# P04_Processor_2_or_3_USB_and_Serial.net
KiCad netlist of a schematic drawn in Altium Designer
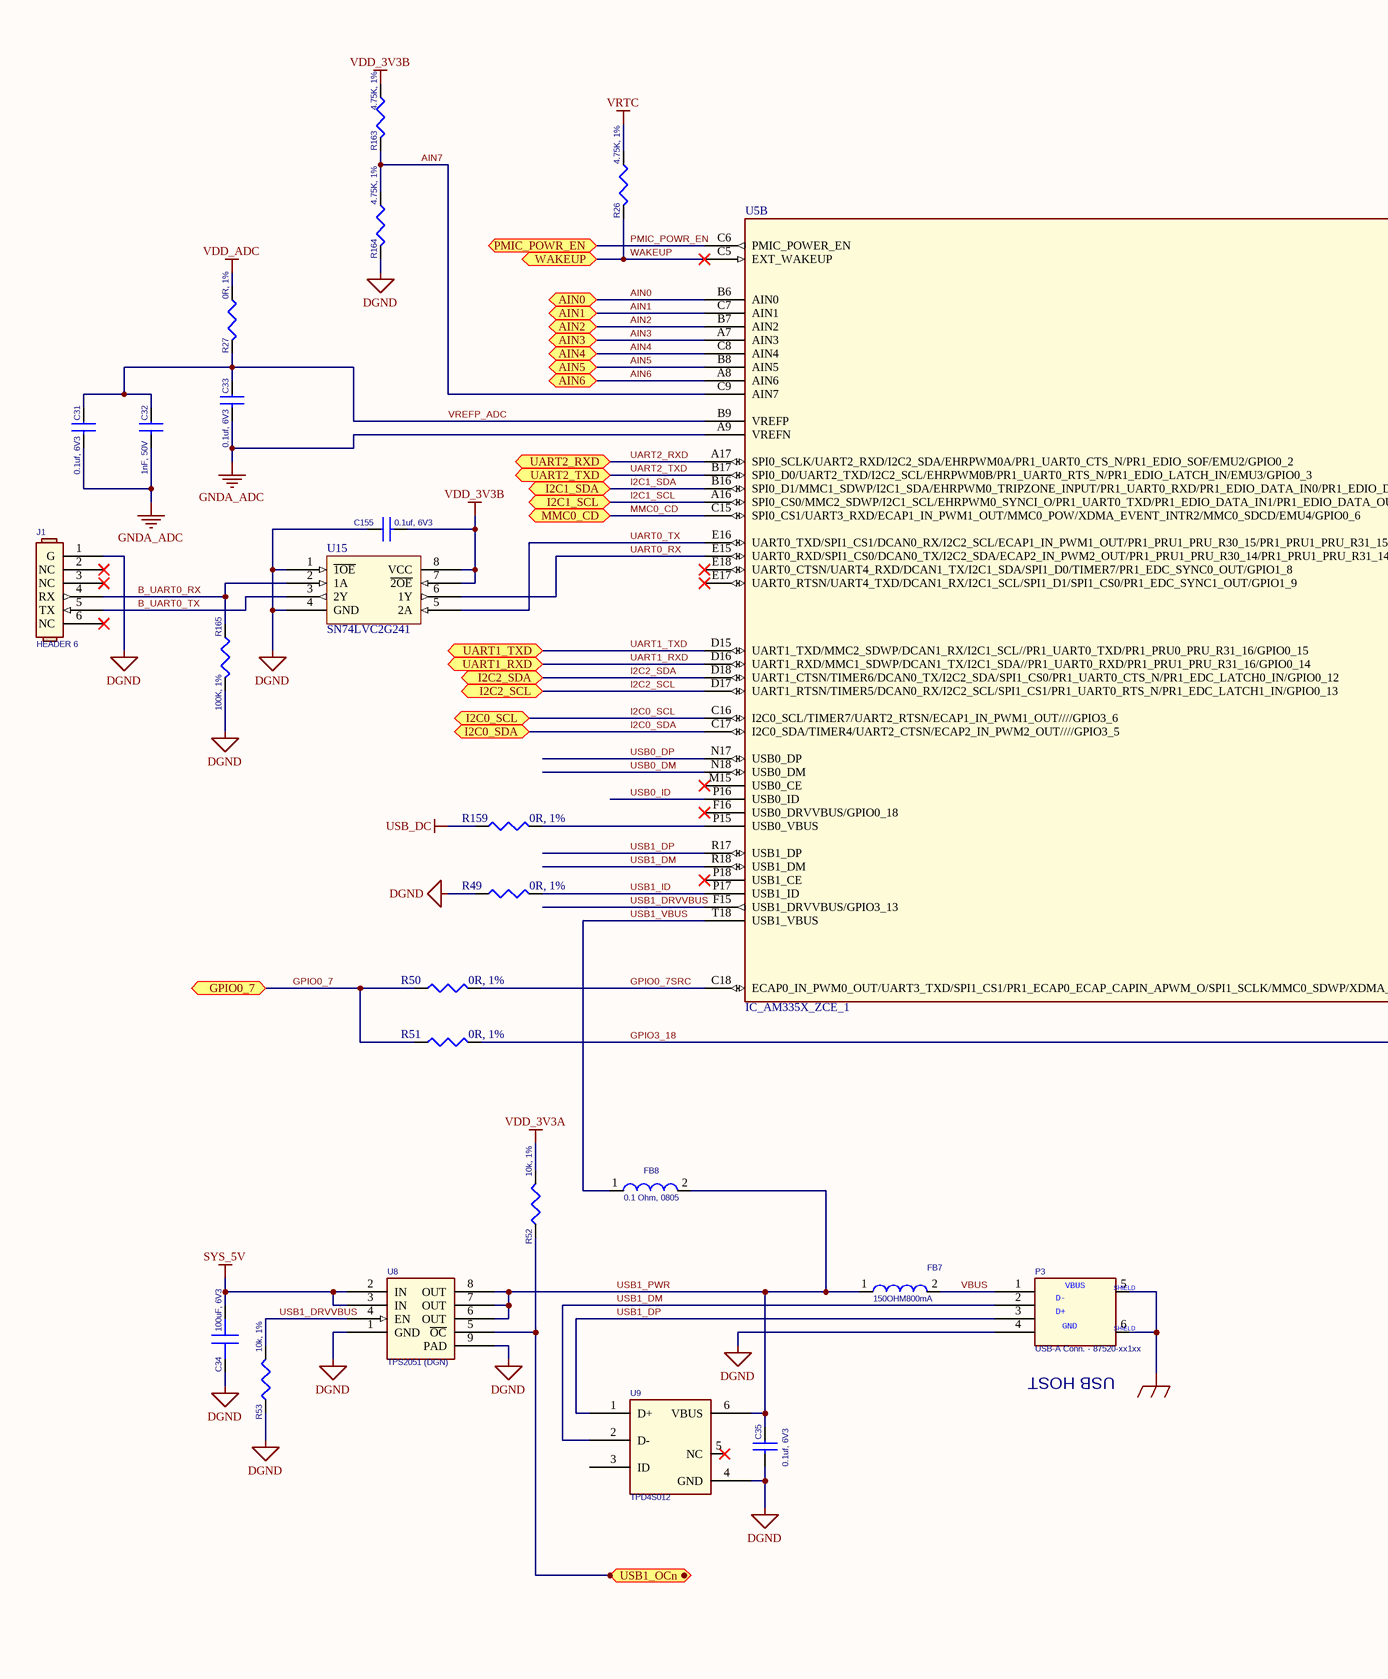
[diagram p0: P04_Processor 2 or 3, USB and Serial.SchDoc, left]
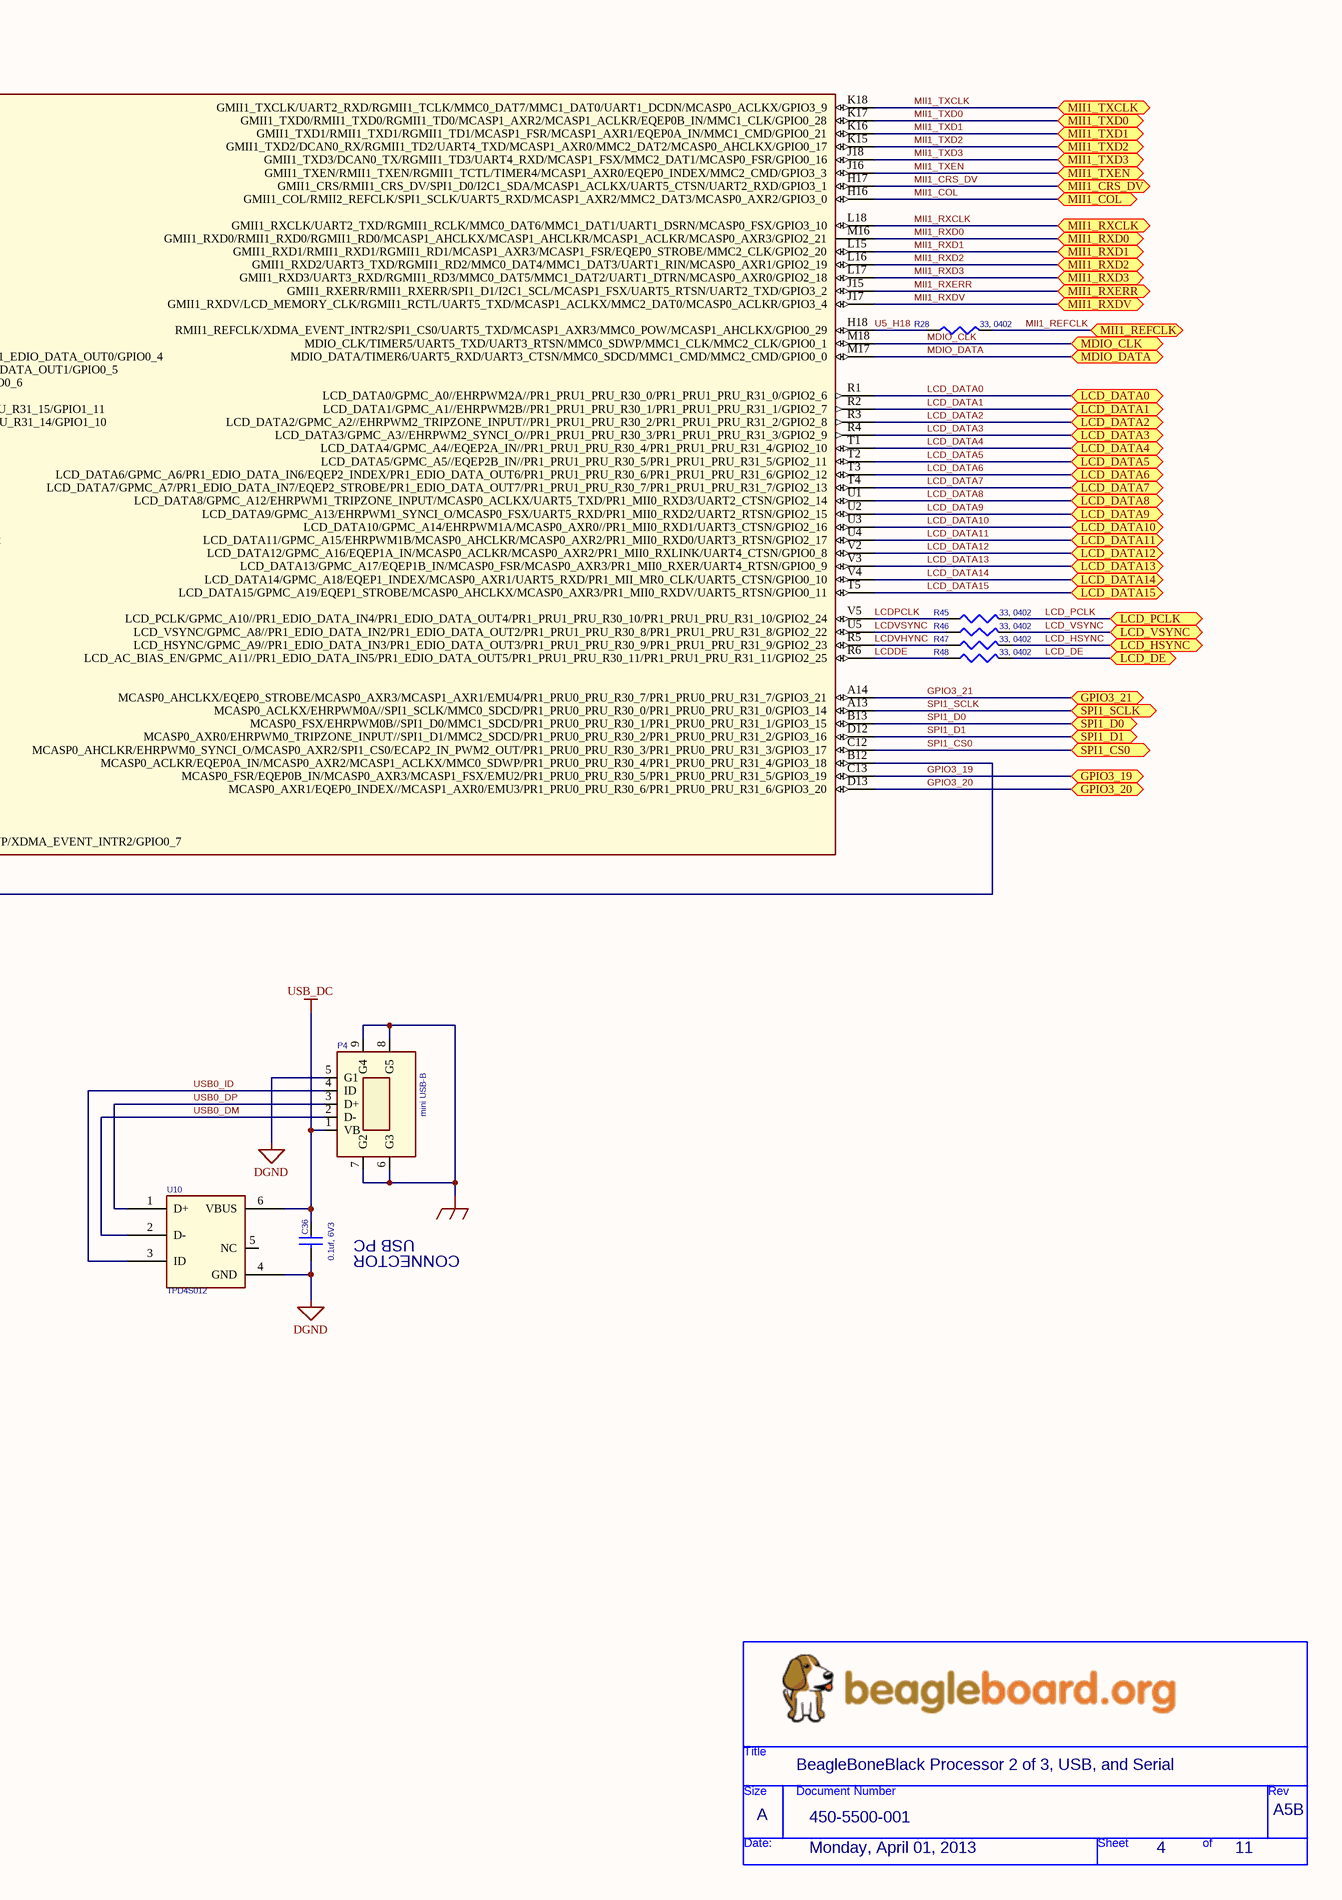
[diagram p1: P04_Processor 2 or 3, USB and Serial.SchDoc, right]

(export (version "E")
  (design (tool "Eeschema 10.0.6"))
  (components
    (comp (ref "C31")
      (value "0.1uf, 6V3")
      (footprint "402")
      (description "CAP CER 0.1UF 6.3V 10% X5R 0402")
      (fields
        (field (name "MANUFACTURER") "TDK Corporation")
        (field (name "MANUFACTURER PART NUMBER") "C1005X5R0J104K050BA")
      )
      (libsource (lib "BEAGLEBONEBLACK_REV A5B") (part "CAP_0.1uF_X7R_16V_10% 0402"))
    )
    (comp (ref "C32")
      (value "1nF, 50V")
      (footprint "402")
      (description "CAP CER 1000PF 16V 10% X7R 0402")
      (fields
        (field (name "MANUFACTURER") "Yageo")
        (field (name "MANUFACTURER PART NUMBER") "CC0402KRX7R7BB102")
      )
      (libsource (lib "BEAGLEBONEBLACK_REV A5B") (part "CAP_0.001_X7R_50V_5%_0402"))
    )
    (comp (ref "C33")
      (value "0.1uf, 6V3")
      (footprint "402")
      (description "CAP CER 0.1UF 6.3V 10% X5R 0402")
      (fields
        (field (name "MANUFACTURER") "TDK Corporation")
        (field (name "MANUFACTURER PART NUMBER") "C1005X5R0J104K050BA")
      )
      (libsource (lib "BEAGLEBONEBLACK_REV A5B") (part "CAP_0.1uF_X7R_16V_10% 0402"))
    )
    (comp (ref "C34")
      (value "100uF, 6V3")
      (footprint "RD205SMD_250D")
      (description "CAP ALUM 100UF 6.3V 20% SMD")
      (fields
        (field (name "MANUFACTURER") "Cornell Dubilier Electronics (CDE)")
        (field (name "MANUFACTURER PART NUMBER") "AVE107M06D16T-F")
      )
      (libsource (lib "BEAGLEBONEBLACK_REV A5B") (part "CAP SMD"))
    )
    (comp (ref "C35")
      (value "0.1uf, 6V3")
      (footprint "402")
      (description "CAP CER 0.1UF 6.3V 10% X5R 0402")
      (fields
        (field (name "MANUFACTURER") "TDK Corporation")
        (field (name "MANUFACTURER PART NUMBER") "C1005X5R0J104K050BA")
      )
      (libsource (lib "BEAGLEBONEBLACK_REV A5B") (part "CAP_0.1uF_X7R_16V_10% 0402"))
    )
    (comp (ref "C36")
      (value "0.1uf, 6V3")
      (footprint "402")
      (description "CAP CER 0.1UF 6.3V 10% X5R 0402")
      (fields
        (field (name "MANUFACTURER") "TDK Corporation")
        (field (name "MANUFACTURER PART NUMBER") "C1005X5R0J104K050BA")
      )
      (libsource (lib "BEAGLEBONEBLACK_REV A5B") (part "CAP_0.1uF_X7R_16V_10% 0402"))
    )
    (comp (ref "C155")
      (value "0.1uf, 6V3")
      (footprint "402")
      (description "CAP CER 0.1UF 6.3V 10% X5R 0402")
      (fields
        (field (name "MANUFACTURER") "TDK Corporation")
        (field (name "MANUFACTURER PART NUMBER") "C1005X5R0J104K050BA")
      )
      (libsource (lib "BEAGLEBONEBLACK_REV A5B") (part "CAP_0.1uF_X7R_16V_10% 0402"))
    )
    (comp (ref "FB7")
      (value "150OHM800mA")
      (footprint "SM-7351-IND-0805")
      (description "FERRITE 800MA 150 OHM 0805 SMD")
      (fields (field (name "MFR") "Steward") (field (name "TIINTPARTNUMBER") "1L0010"))
      (libsource (lib "BEAGLEBONEBLACK_REV A5B") (part "FER_180_200_0"))
    )
    (comp (ref "FB8")
      (value "0.1 Ohm, 0805")
      (footprint "SM-7351-IND-0805")
      (description "RES .10 OHM 1/8W 5% 0805")
      (fields
        (field (name "MANUFACTURER") "CTS Resistor Products")
        (field (name "MANUFACTURER PART NUMBER") "73L3R10J")
      )
      (libsource (lib "BEAGLEBONEBLACK_REV A5B") (part "FER_180_200_0"))
    )
    (comp (ref "J1")
      (value "HEADER 6")
      (footprint "SIP6")
      (description "CONN HEADER 6POS, VERTICAL,  .100 STR TIN")
      (fields
        (field (name "MANUFACTURER") "Samtec Inc")
        (field (name "MANUFACTURER PART NUMBER") "FTR-110-03-G-D-06")
      )
      (libsource (lib "BEAGLEBONEBLACK_REV A5B") (part "HDR_6x1"))
    )
    (comp (ref "P3")
      (value "USB-A Conn. - 87520-xx1xx")
      (description "CONN RCPT USB TYPE A R/A PCB")
      (fields (field (name "MANUFACTURER") "FCI") (field (name "MANUFACTURER PART NUMBER") "87520-0010BLF"))
      (libsource (lib "BEAGLEBONEBLACK_REV A5B") (part "CONN_54819-0578_2"))
    )
    (comp (ref "P4")
      (value "mini USB-B")
      (footprint "USB5MINI_4SHIELDED_SMD-5")
      (description "CONN RCPT USB MINI B R/A SMD")
      (fields (field (name "MANUFACTURER") "KYCON") (field (name "MANUFACTURER PART NUMBER") "0565790576"))
      (libsource (lib "BEAGLEBONEBLACK_REV A5B") (part "MINI-USB-AB-SOCKET"))
    )
    (comp (ref "R26")
      (value "4.75K, 1%")
      (footprint "402")
      (description "RES 4.75K OHM 1/16W 1% 0402 SMD")
      (fields
        (field (name "MANUFACTURER") "Stackpole Electronics Inc")
        (field (name "MANUFACTURER PART NUMBER") "RMCF0402FT4K75")
      )
      (libsource (lib "BEAGLEBONEBLACK_REV A5B") (part "RES_4.75K_1/16W_1%_0402"))
    )
    (comp (ref "R27")
      (value "0R, 1%")
      (footprint "402")
      (description "RES 0.0 OHM 1/16W 0402 SMD")
      (fields
        (field (name "MANUFACTURER") "Yageo")
        (field (name "MANUFACTURER PART NUMBER") "RC0402JR-070RL")
      )
      (libsource (lib "BEAGLEBONEBLACK_REV A5B") (part "RES_0_1/16W_1%_0402"))
    )
    (comp (ref "R28")
      (value "33, 0402")
      (footprint "402")
      (description "RES 33 OHM 1/16W 5% 0402 SMD")
      (fields
        (field (name "MANUFACTURER") "Panasonic Electronic Components")
        (field (name "MANUFACTURER PART NUMBER") "ERJ-2GEJ330X")
      )
      (libsource (lib "BEAGLEBONEBLACK_REV A5B") (part "RES_33_0402"))
    )
    (comp (ref "R45")
      (value "33, 0402")
      (footprint "402")
      (description "RES 33 OHM 1/16W 5% 0402 SMD")
      (fields
        (field (name "MANUFACTURER") "Panasonic Electronic Components")
        (field (name "MANUFACTURER PART NUMBER") "ERJ-2GEJ330X")
      )
      (libsource (lib "BEAGLEBONEBLACK_REV A5B") (part "RES_33_0402"))
    )
    (comp (ref "R46")
      (value "33, 0402")
      (footprint "402")
      (description "RES 33 OHM 1/16W 5% 0402 SMD")
      (fields
        (field (name "MANUFACTURER") "Panasonic Electronic Components")
        (field (name "MANUFACTURER PART NUMBER") "ERJ-2GEJ330X")
      )
      (libsource (lib "BEAGLEBONEBLACK_REV A5B") (part "RES_33_0402"))
    )
    (comp (ref "R47")
      (value "33, 0402")
      (footprint "402")
      (description "RES 33 OHM 1/16W 5% 0402 SMD")
      (fields
        (field (name "MANUFACTURER") "Panasonic Electronic Components")
        (field (name "MANUFACTURER PART NUMBER") "ERJ-2GEJ330X")
      )
      (libsource (lib "BEAGLEBONEBLACK_REV A5B") (part "RES_33_0402"))
    )
    (comp (ref "R48")
      (value "33, 0402")
      (footprint "402")
      (description "RES 33 OHM 1/16W 5% 0402 SMD")
      (fields
        (field (name "MANUFACTURER") "Panasonic Electronic Components")
        (field (name "MANUFACTURER PART NUMBER") "ERJ-2GEJ330X")
      )
      (libsource (lib "BEAGLEBONEBLACK_REV A5B") (part "RES_33_0402"))
    )
    (comp (ref "R49")
      (value "0R, 1%")
      (footprint "402")
      (description "RES 0.0 OHM 1/16W 0402 SMD")
      (fields
        (field (name "MANUFACTURER") "Yageo")
        (field (name "MANUFACTURER PART NUMBER") "RC0402JR-070RL")
      )
      (libsource (lib "BEAGLEBONEBLACK_REV A5B") (part "RES_0_1/16W_1%_0402"))
    )
    (comp (ref "R50")
      (value "0R, 1%")
      (footprint "402")
      (description "RES 0.0 OHM 1/16W 0402 SMD")
      (fields
        (field (name "MANUFACTURER") "Yageo")
        (field (name "MANUFACTURER PART NUMBER") "RC0402JR-070RL")
      )
      (libsource (lib "BEAGLEBONEBLACK_REV A5B") (part "RES_0_1/16W_1%_0402"))
    )
    (comp (ref "R51")
      (value "0R, 1%")
      (footprint "402")
      (description "RES 0.0 OHM 1/16W 0402 SMD")
      (fields
        (field (name "MANUFACTURER") "Yageo")
        (field (name "MANUFACTURER PART NUMBER") "RC0402JR-070RL")
      )
      (libsource (lib "BEAGLEBONEBLACK_REV A5B") (part "RES_0_1/16W_1%_0402"))
    )
    (comp (ref "R52")
      (value "10k, 1%")
      (footprint "402")
      (description "RES 10K OHM 1/16W 5% 0402 SMD")
      (fields
        (field (name "MANUFACTURER") "Rohm Semiconductor")
        (field (name "MANUFACTURER PART NUMBER") "MCR01MZPJ103")
      )
      (libsource (lib "BEAGLEBONEBLACK_REV A5B") (part "RES SMD"))
    )
    (comp (ref "R53")
      (value "10k, 1%")
      (footprint "402")
      (description "RES 10K OHM 1/16W 5% 0402 SMD")
      (fields
        (field (name "MANUFACTURER") "Rohm Semiconductor")
        (field (name "MANUFACTURER PART NUMBER") "MCR01MZPJ103")
      )
      (libsource (lib "BEAGLEBONEBLACK_REV A5B") (part "RES SMD"))
    )
    (comp (ref "R159")
      (value "0R, 1%")
      (footprint "402")
      (description "RES 0.0 OHM 1/16W 0402 SMD")
      (fields
        (field (name "MANUFACTURER") "Yageo")
        (field (name "MANUFACTURER PART NUMBER") "RC0402JR-070RL")
      )
      (libsource (lib "BEAGLEBONEBLACK_REV A5B") (part "RES_0_1/16W_1%_0402"))
    )
    (comp (ref "R163")
      (value "4.75K, 1%")
      (footprint "402")
      (description "RES 4.75K OHM 1/16W 1% 0402 SMD")
      (fields
        (field (name "MANUFACTURER") "Stackpole Electronics Inc")
        (field (name "MANUFACTURER PART NUMBER") "RMCF0402FT4K75")
      )
      (libsource (lib "BEAGLEBONEBLACK_REV A5B") (part "RES_4.75K_1/16W_1%_0402"))
    )
    (comp (ref "R164")
      (value "4.75K, 1%")
      (footprint "402")
      (description "RES 4.75K OHM 1/16W 1% 0402 SMD")
      (fields
        (field (name "MANUFACTURER") "Stackpole Electronics Inc")
        (field (name "MANUFACTURER PART NUMBER") "RMCF0402FT4K75")
      )
      (libsource (lib "BEAGLEBONEBLACK_REV A5B") (part "RES_4.75K_1/16W_1%_0402"))
    )
    (comp (ref "R165")
      (value "100K, 1%")
      (footprint "402")
      (description "RES 100K OHM 1/16W 1% 0402 SMD")
      (fields
        (field (name "MANUFACTURER") "Stackpole Electronics Inc")
        (field (name "MANUFACTURER PART NUMBER") "RMCF0402FT100K")
      )
      (libsource (lib "BEAGLEBONEBLACK_REV A5B") (part "RES_100K_1/16W_1%_0402"))
    )
    (comp (ref "U5")
      (value "IC_AM335X_ZCE_1")
      (footprint "am33xx_15x15")
      (description "SubArctic Cortex A8 Processor 15x15")
      (fields (field (name "MFR") "TI") (field (name "TIINTPARTNUMBER") "1A0242"))
      (libsource (lib "BEAGLEBONEBLACK_REV A5B") (part "IC_AM335X_ZCE_1"))
    )
    (comp (ref "U8")
      (value "TPS2051 (DGN)")
      (description "IC 1.5A PWR DIST SWITCH 8-SOIC")
      (fields
        (field (name "MANUFACTURER") "Texas Instruments")
        (field (name "MANUFACTURER PART NUMBER") "TPS2051BDGNR")
      )
      (libsource (lib "BEAGLEBONEBLACK_REV A5B") (part "TPS2061_0"))
    )
    (comp (ref "U9")
      (value "TPD4S012")
      (footprint "U_6_DRY")
      (description "ESD 4channel USB Interface")
      (fields (field (name "MFR") "TI") (field (name "TIINTPARTNUMBER") "1A0233"))
      (libsource (lib "BEAGLEBONEBLACK_REV A5B") (part "PROT_TPD4S012"))
    )
    (comp (ref "U10")
      (value "TPD4S012")
      (footprint "U_6_DRY")
      (description "ESD 4channel USB Interface")
      (fields (field (name "MFR") "TI") (field (name "TIINTPARTNUMBER") "1A0233"))
      (libsource (lib "BEAGLEBONEBLACK_REV A5B") (part "PROT_TPD4S012"))
    )
    (comp (ref "U15")
      (value "SN74LVC2G241")
      (footprint "U_8_DCU")
      (description "IC BUFF/DVR TRI-ST DL 8VSSOP")
      (fields
        (field (name "MANUFACTURER") "Texas Instruments")
        (field (name "MANUFACTURER PART NUMBER") "SN74LVC2G241DCUR")
      )
      (libsource (lib "BEAGLEBONEBLACK_REV A5B") (part "SN74LVC2G241"))
    )
  )
  (nets
    (net (code "1") (name "/AIN0") (class "Default")
      (node (ref "U5") (pin "B6") (pinfunction "AIN0_B6") (pintype "passive"))
    )
    (net (code "2") (name "/AIN1") (class "Default")
      (node (ref "U5") (pin "C7") (pinfunction "AIN1_C7") (pintype "passive"))
    )
    (net (code "3") (name "/AIN2") (class "Default")
      (node (ref "U5") (pin "B7") (pinfunction "AIN2_B7") (pintype "passive"))
    )
    (net (code "4") (name "/AIN3") (class "Default")
      (node (ref "U5") (pin "A7") (pinfunction "AIN3_A7") (pintype "passive"))
    )
    (net (code "5") (name "/AIN4") (class "Default")
      (node (ref "U5") (pin "C8") (pinfunction "AIN4_C8") (pintype "passive"))
    )
    (net (code "6") (name "/AIN5") (class "Default")
      (node (ref "U5") (pin "B8") (pinfunction "AIN5_B8") (pintype "passive"))
    )
    (net (code "7") (name "/AIN6") (class "Default")
      (node (ref "U5") (pin "A8") (pinfunction "AIN6_A8") (pintype "passive"))
    )
    (net (code "8") (name "/AIN7") (class "Default")
      (node (ref "R163") (pin "2") (pinfunction "2_2") (pintype "passive"))
      (node (ref "R164") (pin "1") (pinfunction "1_1") (pintype "passive"))
      (node (ref "U5") (pin "C9") (pinfunction "AIN7_C9") (pintype "passive"))
    )
    (net (code "9") (name "/B_UART0_RX") (class "Default")
      (node (ref "J1") (pin "4") (pinfunction "RX_4") (pintype "output"))
      (node (ref "R165") (pin "1") (pinfunction "1_1") (pintype "passive"))
      (node (ref "U15") (pin "2") (pinfunction "1A_2") (pintype "input"))
    )
    (net (code "10") (name "/B_UART0_TX") (class "Default")
      (node (ref "J1") (pin "5") (pinfunction "TX_5") (pintype "input"))
      (node (ref "U15") (pin "3") (pinfunction "2Y_3") (pintype "output"))
    )
    (net (code "11") (name "/GPIO0_7") (class "Default")
      (node (ref "R50") (pin "1") (pinfunction "1_1") (pintype "passive"))
      (node (ref "R51") (pin "1") (pinfunction "1_1") (pintype "passive"))
    )
    (net (code "12") (name "/GPIO0_7SRC") (class "Default")
      (node (ref "R50") (pin "2") (pinfunction "2_2") (pintype "passive"))
      (node (ref "U5") (pin "C18") (pinfunction "ECAP0_IN_PWM0_OUT/UART3_TXD/SPI1_CS1/PR1_ECAP0_ECAP_CAPIN_APWM_O/SPI1_SCLK/MMC0_SDWP/XDMA_EVENT_INTR2/GPIO0_7_C18") (pintype "bidirectional"))
    )
    (net (code "13") (name "/GPIO3_18") (class "Default")
      (node (ref "R51") (pin "2") (pinfunction "2_2") (pintype "passive"))
      (node (ref "U5") (pin "B12") (pinfunction "MCASP0_ACLKR/EQEP0A_IN/MCASP0_AXR2/MCASP1_ACLKX/MMC0_SDWP/PR1_PRU0_PRU_R30_4/PR1_PRU0_PRU_R31_4/GPIO3_18_B12") (pintype "bidirectional"))
    )
    (net (code "14") (name "/GPIO3_19") (class "Default")
      (node (ref "U5") (pin "C13") (pinfunction "MCASP0_FSR/EQEP0B_IN/MCASP0_AXR3/MCASP1_FSX/EMU2/PR1_PRU0_PRU_R30_5/PR1_PRU0_PRU_R31_5/GPIO3_19_C13") (pintype "bidirectional"))
    )
    (net (code "15") (name "/GPIO3_20") (class "Default")
      (node (ref "U5") (pin "D13") (pinfunction "MCASP0_AXR1/EQEP0_INDEX//MCASP1_AXR0/EMU3/PR1_PRU0_PRU_R30_6/PR1_PRU0_PRU_R31_6/GPIO3_20_D13") (pintype "bidirectional"))
    )
    (net (code "16") (name "/GPIO3_21") (class "Default")
      (node (ref "U5") (pin "A14") (pinfunction "MCASP0_AHCLKX/EQEP0_STROBE/MCASP0_AXR3/MCASP1_AXR1/EMU4/PR1_PRU0_PRU_R30_7/PR1_PRU0_PRU_R31_7/GPIO3_21_A14") (pintype "bidirectional"))
    )
    (net (code "17") (name "/I2C0_SCL") (class "Default")
      (node (ref "U5") (pin "C16") (pinfunction "I2C0_SCL/TIMER7/UART2_RTSN/ECAP1_IN_PWM1_OUT////GPIO3_6_C16") (pintype "bidirectional"))
    )
    (net (code "18") (name "/I2C0_SDA") (class "Default")
      (node (ref "U5") (pin "C17") (pinfunction "I2C0_SDA/TIMER4/UART2_CTSN/ECAP2_IN_PWM2_OUT////GPIO3_5_C17") (pintype "bidirectional"))
    )
    (net (code "19") (name "/I2C1_SCL") (class "Default")
      (node (ref "U5") (pin "A16") (pinfunction "SPI0_CS0/MMC2_SDWP/I2C1_SCL/EHRPWM0_SYNCI_O/PR1_UART0_TXD/PR1_EDIO_DATA_IN1/PR1_EDIO_DATA_OUT1/GPIO0_5_A16") (pintype "bidirectional"))
    )
    (net (code "20") (name "/I2C1_SDA") (class "Default")
      (node (ref "U5") (pin "B16") (pinfunction "SPI0_D1/MMC1_SDWP/I2C1_SDA/EHRPWM0_TRIPZONE_INPUT/PR1_UART0_RXD/PR1_EDIO_DATA_IN0/PR1_EDIO_DATA_OUT0/GPIO0_4_B16") (pintype "bidirectional"))
    )
    (net (code "21") (name "/I2C2_SCL") (class "Default")
      (node (ref "U5") (pin "D17") (pinfunction "UART1_RTSN/TIMER5/DCAN0_RX/I2C2_SCL/SPI1_CS1/PR1_UART0_RTS_N/PR1_EDC_LATCH1_IN/GPIO0_13_D17") (pintype "bidirectional"))
    )
    (net (code "22") (name "/I2C2_SDA") (class "Default")
      (node (ref "U5") (pin "D18") (pinfunction "UART1_CTSN/TIMER6/DCAN0_TX/I2C2_SDA/SPI1_CS0/PR1_UART0_CTS_N/PR1_EDC_LATCH0_IN/GPIO0_12_D18") (pintype "bidirectional"))
    )
    (net (code "23") (name "/LCDDE") (class "Default")
      (node (ref "R48") (pin "1") (pinfunction "1_1") (pintype "passive"))
      (node (ref "U5") (pin "R6") (pinfunction "LCD_AC_BIAS_EN/GPMC_A11//PR1_EDIO_DATA_IN5/PR1_EDIO_DATA_OUT5/PR1_PRU1_PRU_R30_11/PR1_PRU1_PRU_R31_11/GPIO2_25_R6") (pintype "bidirectional"))
    )
    (net (code "24") (name "/LCDPCLK") (class "Default")
      (node (ref "R45") (pin "1") (pinfunction "1_1") (pintype "passive"))
      (node (ref "U5") (pin "V5") (pinfunction "LCD_PCLK/GPMC_A10//PR1_EDIO_DATA_IN4/PR1_EDIO_DATA_OUT4/PR1_PRU1_PRU_R30_10/PR1_PRU1_PRU_R31_10/GPIO2_24_V5") (pintype "bidirectional"))
    )
    (net (code "25") (name "/LCDVHYNC") (class "Default")
      (node (ref "R47") (pin "1") (pinfunction "1_1") (pintype "passive"))
      (node (ref "U5") (pin "R5") (pinfunction "LCD_HSYNC/GPMC_A9//PR1_EDIO_DATA_IN3/PR1_EDIO_DATA_OUT3/PR1_PRU1_PRU_R30_9/PR1_PRU1_PRU_R31_9/GPIO2_23_R5") (pintype "bidirectional"))
    )
    (net (code "26") (name "/LCDVSYNC") (class "Default")
      (node (ref "R46") (pin "1") (pinfunction "1_1") (pintype "passive"))
      (node (ref "U5") (pin "U5") (pinfunction "LCD_VSYNC/GPMC_A8//PR1_EDIO_DATA_IN2/PR1_EDIO_DATA_OUT2/PR1_PRU1_PRU_R30_8/PR1_PRU1_PRU_R31_8/GPIO2_22_U5") (pintype "bidirectional"))
    )
    (net (code "27") (name "/LCD_DATA0") (class "Default")
      (node (ref "U5") (pin "R1") (pinfunction "LCD_DATA0/GPMC_A0//EHRPWM2A//PR1_PRU1_PRU_R30_0/PR1_PRU1_PRU_R31_0/GPIO2_6_R1") (pintype "output"))
    )
    (net (code "28") (name "/LCD_DATA1") (class "Default")
      (node (ref "U5") (pin "R2") (pinfunction "LCD_DATA1/GPMC_A1//EHRPWM2B//PR1_PRU1_PRU_R30_1/PR1_PRU1_PRU_R31_1/GPIO2_7_R2") (pintype "output"))
    )
    (net (code "29") (name "/LCD_DATA2") (class "Default")
      (node (ref "U5") (pin "R3") (pinfunction "LCD_DATA2/GPMC_A2//EHRPWM2_TRIPZONE_INPUT//PR1_PRU1_PRU_R30_2/PR1_PRU1_PRU_R31_2/GPIO2_8_R3") (pintype "output"))
    )
    (net (code "30") (name "/LCD_DATA3") (class "Default")
      (node (ref "U5") (pin "R4") (pinfunction "LCD_DATA3/GPMC_A3//EHRPWM2_SYNCI_O//PR1_PRU1_PRU_R30_3/PR1_PRU1_PRU_R31_3/GPIO2_9_R4") (pintype "output"))
    )
    (net (code "31") (name "/LCD_DATA4") (class "Default")
      (node (ref "U5") (pin "T1") (pinfunction "LCD_DATA4/GPMC_A4//EQEP2A_IN//PR1_PRU1_PRU_R30_4/PR1_PRU1_PRU_R31_4/GPIO2_10_T1") (pintype "bidirectional"))
    )
    (net (code "32") (name "/LCD_DATA5") (class "Default")
      (node (ref "U5") (pin "T2") (pinfunction "LCD_DATA5/GPMC_A5//EQEP2B_IN//PR1_PRU1_PRU_R30_5/PR1_PRU1_PRU_R31_5/GPIO2_11_T2") (pintype "bidirectional"))
    )
    (net (code "33") (name "/LCD_DATA6") (class "Default")
      (node (ref "U5") (pin "T3") (pinfunction "LCD_DATA6/GPMC_A6/PR1_EDIO_DATA_IN6/EQEP2_INDEX/PR1_EDIO_DATA_OUT6/PR1_PRU1_PRU_R30_6/PR1_PRU1_PRU_R31_6/GPIO2_12_T3") (pintype "bidirectional"))
    )
    (net (code "34") (name "/LCD_DATA7") (class "Default")
      (node (ref "U5") (pin "T4") (pinfunction "LCD_DATA7/GPMC_A7/PR1_EDIO_DATA_IN7/EQEP2_STROBE/PR1_EDIO_DATA_OUT7/PR1_PRU1_PRU_R30_7/PR1_PRU1_PRU_R31_7/GPIO2_13_T4") (pintype "bidirectional"))
    )
    (net (code "35") (name "/LCD_DATA8") (class "Default")
      (node (ref "U5") (pin "U1") (pinfunction "LCD_DATA8/GPMC_A12/EHRPWM1_TRIPZONE_INPUT/MCASP0_ACLKX/UART5_TXD/PR1_MII0_RXD3/UART2_CTSN/GPIO2_14_U1") (pintype "bidirectional"))
    )
    (net (code "36") (name "/LCD_DATA9") (class "Default")
      (node (ref "U5") (pin "U2") (pinfunction "LCD_DATA9/GPMC_A13/EHRPWM1_SYNCI_O/MCASP0_FSX/UART5_RXD/PR1_MII0_RXD2/UART2_RTSN/GPIO2_15_U2") (pintype "bidirectional"))
    )
    (net (code "37") (name "/LCD_DATA10") (class "Default")
      (node (ref "U5") (pin "U3") (pinfunction "LCD_DATA10/GPMC_A14/EHRPWM1A/MCASP0_AXR0//PR1_MII0_RXD1/UART3_CTSN/GPIO2_16_U3") (pintype "bidirectional"))
    )
    (net (code "38") (name "/LCD_DATA11") (class "Default")
      (node (ref "U5") (pin "U4") (pinfunction "LCD_DATA11/GPMC_A15/EHRPWM1B/MCASP0_AHCLKR/MCASP0_AXR2/PR1_MII0_RXD0/UART3_RTSN/GPIO2_17_U4") (pintype "bidirectional"))
    )
    (net (code "39") (name "/LCD_DATA12") (class "Default")
      (node (ref "U5") (pin "V2") (pinfunction "LCD_DATA12/GPMC_A16/EQEP1A_IN/MCASP0_ACLKR/MCASP0_AXR2/PR1_MII0_RXLINK/UART4_CTSN/GPIO0_8_V2") (pintype "bidirectional"))
    )
    (net (code "40") (name "/LCD_DATA13") (class "Default")
      (node (ref "U5") (pin "V3") (pinfunction "LCD_DATA13/GPMC_A17/EQEP1B_IN/MCASP0_FSR/MCASP0_AXR3/PR1_MII0_RXER/UART4_RTSN/GPIO0_9_V3") (pintype "bidirectional"))
    )
    (net (code "41") (name "/LCD_DATA14") (class "Default")
      (node (ref "U5") (pin "V4") (pinfunction "LCD_DATA14/GPMC_A18/EQEP1_INDEX/MCASP0_AXR1/UART5_RXD/PR1_MII_MR0_CLK/UART5_CTSN/GPIO0_10_V4") (pintype "bidirectional"))
    )
    (net (code "42") (name "/LCD_DATA15") (class "Default")
      (node (ref "U5") (pin "T5") (pinfunction "LCD_DATA15/GPMC_A19/EQEP1_STROBE/MCASP0_AHCLKX/MCASP0_AXR3/PR1_MII0_RXDV/UART5_RTSN/GPIO0_11_T5") (pintype "bidirectional"))
    )
    (net (code "43") (name "/LCD_DE") (class "Default")
      (node (ref "R48") (pin "2") (pinfunction "2_2") (pintype "passive"))
    )
    (net (code "44") (name "/LCD_HSYNC") (class "Default")
      (node (ref "R47") (pin "2") (pinfunction "2_2") (pintype "passive"))
    )
    (net (code "45") (name "/LCD_PCLK") (class "Default")
      (node (ref "R45") (pin "2") (pinfunction "2_2") (pintype "passive"))
    )
    (net (code "46") (name "/LCD_VSYNC") (class "Default")
      (node (ref "R46") (pin "2") (pinfunction "2_2") (pintype "passive"))
    )
    (net (code "47") (name "/MDIO_CLK") (class "Default")
      (node (ref "U5") (pin "M18") (pinfunction "MDIO_CLK/TIMER5/UART5_TXD/UART3_RTSN/MMC0_SDWP/MMC1_CLK/MMC2_CLK/GPIO0_1_M18") (pintype "bidirectional"))
    )
    (net (code "48") (name "/MDIO_DATA") (class "Default")
      (node (ref "U5") (pin "M17") (pinfunction "MDIO_DATA/TIMER6/UART5_RXD/UART3_CTSN/MMC0_SDCD/MMC1_CMD/MMC2_CMD/GPIO0_0_M17") (pintype "bidirectional"))
    )
    (net (code "49") (name "/MII1_COL") (class "Default")
      (node (ref "U5") (pin "H16") (pinfunction "GMII1_COL/RMII2_REFCLK/SPI1_SCLK/UART5_RXD/MCASP1_AXR2/MMC2_DAT3/MCASP0_AXR2/GPIO3_0_H16") (pintype "bidirectional"))
    )
    (net (code "50") (name "/MII1_CRS_DV") (class "Default")
      (node (ref "U5") (pin "H17") (pinfunction "GMII1_CRS/RMII1_CRS_DV/SPI1_D0/I2C1_SDA/MCASP1_ACLKX/UART5_CTSN/UART2_RXD/GPIO3_1_H17") (pintype "bidirectional"))
    )
    (net (code "51") (name "/MII1_REFCLK") (class "Default")
      (node (ref "R28") (pin "2") (pinfunction "2_2") (pintype "passive"))
    )
    (net (code "52") (name "/MII1_RXCLK") (class "Default")
      (node (ref "U5") (pin "L18") (pinfunction "GMII1_RXCLK/UART2_TXD/RGMII1_RCLK/MMC0_DAT6/MMC1_DAT1/UART1_DSRN/MCASP0_FSX/GPIO3_10_L18") (pintype "bidirectional"))
    )
    (net (code "53") (name "/MII1_RXD0") (class "Default")
      (node (ref "U5") (pin "M16") (pinfunction "GMII1_RXD0/RMII1_RXD0/RGMII1_RD0/MCASP1_AHCLKX/MCASP1_AHCLKR/MCASP1_ACLKR/MCASP0_AXR3/GPIO2_21_M16") (pintype "passive"))
    )
    (net (code "54") (name "/MII1_RXD1") (class "Default")
      (node (ref "U5") (pin "L15") (pinfunction "GMII1_RXD1/RMII1_RXD1/RGMII1_RD1/MCASP1_AXR3/MCASP1_FSR/EQEP0_STROBE/MMC2_CLK/GPIO2_20_L15") (pintype "bidirectional"))
    )
    (net (code "55") (name "/MII1_RXD2") (class "Default")
      (node (ref "U5") (pin "L16") (pinfunction "GMII1_RXD2/UART3_TXD/RGMII1_RD2/MMC0_DAT4/MMC1_DAT3/UART1_RIN/MCASP0_AXR1/GPIO2_19_L16") (pintype "bidirectional"))
    )
    (net (code "56") (name "/MII1_RXD3") (class "Default")
      (node (ref "U5") (pin "L17") (pinfunction "GMII1_RXD3/UART3_RXD/RGMII1_RD3/MMC0_DAT5/MMC1_DAT2/UART1_DTRN/MCASP0_AXR0/GPIO2_18_L17") (pintype "bidirectional"))
    )
    (net (code "57") (name "/MII1_RXDV") (class "Default")
      (node (ref "U5") (pin "J17") (pinfunction "GMII1_RXDV/LCD_MEMORY_CLK/RGMII1_RCTL/UART5_TXD/MCASP1_ACLKX/MMC2_DAT0/MCASP0_ACLKR/GPIO3_4_J17") (pintype "bidirectional"))
    )
    (net (code "58") (name "/MII1_RXERR") (class "Default")
      (node (ref "U5") (pin "J15") (pinfunction "GMII1_RXERR/RMII1_RXERR/SPI1_D1/I2C1_SCL/MCASP1_FSX/UART5_RTSN/UART2_TXD/GPIO3_2_J15") (pintype "bidirectional"))
    )
    (net (code "59") (name "/MII1_TXCLK") (class "Default")
      (node (ref "U5") (pin "K18") (pinfunction "GMII1_TXCLK/UART2_RXD/RGMII1_TCLK/MMC0_DAT7/MMC1_DAT0/UART1_DCDN/MCASP0_ACLKX/GPIO3_9_K18") (pintype "bidirectional"))
    )
    (net (code "60") (name "/MII1_TXD0") (class "Default")
      (node (ref "U5") (pin "K17") (pinfunction "GMII1_TXD0/RMII1_TXD0/RGMII1_TD0/MCASP1_AXR2/MCASP1_ACLKR/EQEP0B_IN/MMC1_CLK/GPIO0_28_K17") (pintype "bidirectional"))
    )
    (net (code "61") (name "/MII1_TXD1") (class "Default")
      (node (ref "U5") (pin "K16") (pinfunction "GMII1_TXD1/RMII1_TXD1/RGMII1_TD1/MCASP1_FSR/MCASP1_AXR1/EQEP0A_IN/MMC1_CMD/GPIO0_21_K16") (pintype "bidirectional"))
    )
    (net (code "62") (name "/MII1_TXD2") (class "Default")
      (node (ref "U5") (pin "K15") (pinfunction "GMII1_TXD2/DCAN0_RX/RGMII1_TD2/UART4_TXD/MCASP1_AXR0/MMC2_DAT2/MCASP0_AHCLKX/GPIO0_17_K15") (pintype "bidirectional"))
    )
    (net (code "63") (name "/MII1_TXD3") (class "Default")
      (node (ref "U5") (pin "J18") (pinfunction "GMII1_TXD3/DCAN0_TX/RGMII1_TD3/UART4_RXD/MCASP1_FSX/MMC2_DAT1/MCASP0_FSR/GPIO0_16_J18") (pintype "bidirectional"))
    )
    (net (code "64") (name "/MII1_TXEN") (class "Default")
      (node (ref "U5") (pin "J16") (pinfunction "GMII1_TXEN/RMII1_TXEN/RGMII1_TCTL/TIMER4/MCASP1_AXR0/EQEP0_INDEX/MMC2_CMD/GPIO3_3_J16") (pintype "bidirectional"))
    )
    (net (code "65") (name "/MMC0_CD") (class "Default")
      (node (ref "U5") (pin "C15") (pinfunction "SPI0_CS1/UART3_RXD/ECAP1_IN_PWM1_OUT/MMC0_POW/XDMA_EVENT_INTR2/MMC0_SDCD/EMU4/GPIO0_6_C15") (pintype "bidirectional"))
    )
    (net (code "66") (name "/PMIC_POWR_EN") (class "Default")
      (node (ref "U5") (pin "C6") (pinfunction "PMIC_POWER_EN_C6") (pintype "output"))
    )
    (net (code "67") (name "/SPI1_CS0") (class "Default")
      (node (ref "U5") (pin "C12") (pinfunction "MCASP0_AHCLKR/EHRPWM0_SYNCI_O/MCASP0_AXR2/SPI1_CS0/ECAP2_IN_PWM2_OUT/PR1_PRU0_PRU_R30_3/PR1_PRU0_PRU_R31_3/GPIO3_17_C12") (pintype "bidirectional"))
    )
    (net (code "68") (name "/SPI1_D0") (class "Default")
      (node (ref "U5") (pin "B13") (pinfunction "MCASP0_FSX/EHRPWM0B//SPI1_D0/MMC1_SDCD/PR1_PRU0_PRU_R30_1/PR1_PRU0_PRU_R31_1/GPIO3_15_B13") (pintype "bidirectional"))
    )
    (net (code "69") (name "/SPI1_D1") (class "Default")
      (node (ref "U5") (pin "D12") (pinfunction "MCASP0_AXR0/EHRPWM0_TRIPZONE_INPUT//SPI1_D1/MMC2_SDCD/PR1_PRU0_PRU_R30_2/PR1_PRU0_PRU_R31_2/GPIO3_16_D12") (pintype "bidirectional"))
    )
    (net (code "70") (name "/SPI1_SCLK") (class "Default")
      (node (ref "U5") (pin "A13") (pinfunction "MCASP0_ACLKX/EHRPWM0A//SPI1_SCLK/MMC0_SDCD/PR1_PRU0_PRU_R30_0/PR1_PRU0_PRU_R31_0/GPIO3_14_A13") (pintype "bidirectional"))
    )
    (net (code "71") (name "/U5_H18") (class "Default")
      (node (ref "R28") (pin "1") (pinfunction "1_1") (pintype "passive"))
      (node (ref "U5") (pin "H18") (pinfunction "RMII1_REFCLK/XDMA_EVENT_INTR2/SPI1_CS0/UART5_TXD/MCASP1_AXR3/MMC0_POW/MCASP1_AHCLKX/GPIO0_29_H18") (pintype "bidirectional"))
    )
    (net (code "72") (name "/UART0_RX") (class "Default")
      (node (ref "U15") (pin "6") (pinfunction "1Y_6") (pintype "output"))
      (node (ref "U5") (pin "E15") (pinfunction "UART0_RXD/SPI1_CS0/DCAN0_TX/I2C2_SDA/ECAP2_IN_PWM2_OUT/PR1_PRU1_PRU_R30_14/PR1_PRU1_PRU_R31_14/GPIO1_10_E15") (pintype "bidirectional"))
    )
    (net (code "73") (name "/UART0_TX") (class "Default")
      (node (ref "U15") (pin "5") (pinfunction "2A_5") (pintype "input"))
      (node (ref "U5") (pin "E16") (pinfunction "UART0_TXD/SPI1_CS1/DCAN0_RX/I2C2_SCL/ECAP1_IN_PWM1_OUT/PR1_PRU1_PRU_R30_15/PR1_PRU1_PRU_R31_15/GPIO1_11_E16") (pintype "bidirectional"))
    )
    (net (code "74") (name "/UART1_RXD") (class "Default")
      (node (ref "U5") (pin "D16") (pinfunction "UART1_RXD/MMC1_SDWP/DCAN1_TX/I2C1_SDA//PR1_UART0_RXD/PR1_PRU1_PRU_R31_16/GPIO0_14_D16") (pintype "bidirectional"))
    )
    (net (code "75") (name "/UART1_TXD") (class "Default")
      (node (ref "U5") (pin "D15") (pinfunction "UART1_TXD/MMC2_SDWP/DCAN1_RX/I2C1_SCL//PR1_UART0_TXD/PR1_PRU0_PRU_R31_16/GPIO0_15_D15") (pintype "bidirectional"))
    )
    (net (code "76") (name "/UART2_RXD") (class "Default")
      (node (ref "U5") (pin "A17") (pinfunction "SPI0_SCLK/UART2_RXD/I2C2_SDA/EHRPWM0A/PR1_UART0_CTS_N/PR1_EDIO_SOF/EMU2/GPIO0_2_A17") (pintype "bidirectional"))
    )
    (net (code "77") (name "/UART2_TXD") (class "Default")
      (node (ref "U5") (pin "B17") (pinfunction "SPI0_D0/UART2_TXD/I2C2_SCL/EHRPWM0B/PR1_UART0_RTS_N/PR1_EDIO_LATCH_IN/EMU3/GPIO0_3_B17") (pintype "bidirectional"))
    )
    (net (code "78") (name "/USB0_DM") (class "Default")
      (node (ref "P4") (pin "2") (pinfunction "D-_2") (pintype "passive"))
      (node (ref "U10") (pin "2") (pinfunction "D-_2") (pintype "passive"))
      (node (ref "U5") (pin "N18") (pinfunction "USB0_DM_N18") (pintype "bidirectional"))
    )
    (net (code "79") (name "/USB0_DP") (class "Default")
      (node (ref "P4") (pin "3") (pinfunction "D+_3") (pintype "passive"))
      (node (ref "U10") (pin "1") (pinfunction "D+_1") (pintype "passive"))
      (node (ref "U5") (pin "N17") (pinfunction "USB0_DP_N17") (pintype "bidirectional"))
    )
    (net (code "80") (name "/USB0_ID") (class "Default")
      (node (ref "P4") (pin "4") (pinfunction "ID_4") (pintype "passive"))
      (node (ref "U10") (pin "3") (pinfunction "ID_3") (pintype "passive"))
      (node (ref "U5") (pin "P16") (pinfunction "USB0_ID_P16") (pintype "passive"))
    )
    (net (code "81") (name "/USB1_DM") (class "Default")
      (node (ref "P3") (pin "2") (pinfunction "P2_2") (pintype "passive"))
      (node (ref "U5") (pin "R18") (pinfunction "USB1_DM_R18") (pintype "bidirectional"))
      (node (ref "U9") (pin "2") (pinfunction "D-_2") (pintype "passive"))
    )
    (net (code "82") (name "/USB1_DP") (class "Default")
      (node (ref "P3") (pin "3") (pinfunction "P3_3") (pintype "passive"))
      (node (ref "U5") (pin "R17") (pinfunction "USB1_DP_R17") (pintype "bidirectional"))
      (node (ref "U9") (pin "1") (pinfunction "D+_1") (pintype "passive"))
    )
    (net (code "83") (name "/USB1_DRVVBUS") (class "Default")
      (node (ref "R53") (pin "1") (pinfunction "P1_1") (pintype "passive"))
      (node (ref "U5") (pin "F15") (pinfunction "USB1_DRVVBUS/GPIO3_13_F15") (pintype "output"))
      (node (ref "U8") (pin "4") (pinfunction "EN_4") (pintype "input"))
    )
    (net (code "84") (name "/USB1_ID") (class "Default")
      (node (ref "R49") (pin "2") (pinfunction "2_2") (pintype "passive"))
      (node (ref "U5") (pin "P17") (pinfunction "USB1_ID_P17") (pintype "passive"))
    )
    (net (code "85") (name "/USB1_OCn") (class "Default")
      (node (ref "R52") (pin "2") (pinfunction "P2_2") (pintype "passive"))
      (node (ref "U8") (pin "5") (pinfunction "~{OC}_5") (pintype "passive"))
    )
    (net (code "86") (name "/USB1_PWR") (class "Default")
      (node (ref "C35") (pin "1") (pinfunction "1_1") (pintype "passive"))
      (node (ref "FB7") (pin "1") (pinfunction "1_1") (pintype "passive"))
      (node (ref "FB8") (pin "2") (pinfunction "2_2") (pintype "passive"))
      (node (ref "U8") (pin "6") (pinfunction "OUT_6") (pintype "power_in"))
      (node (ref "U8") (pin "7") (pinfunction "OUT_7") (pintype "power_in"))
      (node (ref "U8") (pin "8") (pinfunction "OUT_8") (pintype "power_in"))
      (node (ref "U9") (pin "6") (pinfunction "VBUS_6") (pintype "power_in"))
    )
    (net (code "87") (name "/USB1_VBUS") (class "Default")
      (node (ref "FB8") (pin "1") (pinfunction "1_1") (pintype "passive"))
      (node (ref "U5") (pin "T18") (pinfunction "USB1_VBUS_T18") (pintype "passive"))
    )
    (net (code "88") (name "/VBUS") (class "Default")
      (node (ref "FB7") (pin "2") (pinfunction "2_2") (pintype "passive"))
      (node (ref "P3") (pin "1") (pinfunction "P1_1") (pintype "passive"))
    )
    (net (code "89") (name "/VREFP_ADC") (class "Default")
      (node (ref "C31") (pin "1") (pinfunction "1_1") (pintype "passive"))
      (node (ref "C32") (pin "1") (pinfunction "1_1") (pintype "passive"))
      (node (ref "C33") (pin "1") (pinfunction "1_1") (pintype "passive"))
      (node (ref "R27") (pin "2") (pinfunction "2_2") (pintype "passive"))
      (node (ref "U5") (pin "B9") (pinfunction "VREFP_B9") (pintype "passive"))
    )
    (net (code "90") (name "/WAKEUP") (class "Default")
      (node (ref "R26") (pin "2") (pinfunction "2_2") (pintype "passive"))
      (node (ref "U5") (pin "C5") (pinfunction "EXT_WAKEUP_C5") (pintype "input"))
    )
    (net (code "91") (name "DGND") (class "Default")
      (node (ref "C155") (pin "1") (pinfunction "1_1") (pintype "passive"))
      (node (ref "C34") (pin "2") (pinfunction "2_2") (pintype "passive"))
      (node (ref "C35") (pin "2") (pinfunction "2_2") (pintype "passive"))
      (node (ref "C36") (pin "2") (pinfunction "2_2") (pintype "passive"))
      (node (ref "J1") (pin "1") (pinfunction "G_1") (pintype "power_in"))
      (node (ref "P3") (pin "4") (pinfunction "P4_4") (pintype "passive"))
      (node (ref "P4") (pin "5") (pinfunction "G1_5") (pintype "passive"))
      (node (ref "R164") (pin "2") (pinfunction "2_2") (pintype "passive"))
      (node (ref "R165") (pin "2") (pinfunction "2_2") (pintype "passive"))
      (node (ref "R49") (pin "1") (pinfunction "1_1") (pintype "passive"))
      (node (ref "R53") (pin "2") (pinfunction "P2_2") (pintype "passive"))
      (node (ref "U10") (pin "4") (pinfunction "GND_4") (pintype "power_in"))
      (node (ref "U15") (pin "1") (pinfunction "~{1OE}_1") (pintype "input"))
      (node (ref "U15") (pin "4") (pinfunction "GND_4") (pintype "power_in"))
      (node (ref "U8") (pin "1") (pinfunction "GND_1") (pintype "power_in"))
      (node (ref "U8") (pin "9") (pinfunction "PAD_9") (pintype "passive"))
      (node (ref "U9") (pin "4") (pinfunction "GND_4") (pintype "power_in"))
    )
    (net (code "92") (name "GNDA_ADC") (class "Default")
      (node (ref "C31") (pin "2") (pinfunction "2_2") (pintype "passive"))
      (node (ref "C32") (pin "2") (pinfunction "2_2") (pintype "passive"))
      (node (ref "C33") (pin "2") (pinfunction "2_2") (pintype "passive"))
      (node (ref "U5") (pin "A9") (pinfunction "VREFN_A9") (pintype "passive"))
    )
    (net (code "93") (name "GND_EARTH") (class "Default")
      (node (ref "P3") (pin "5") (pinfunction "SHELD1_5") (pintype "passive"))
      (node (ref "P3") (pin "6") (pinfunction "PAD4_6") (pintype "passive"))
      (node (ref "P4") (pin "6") (pinfunction "G3_6") (pintype "passive"))
      (node (ref "P4") (pin "7") (pinfunction "G2_7") (pintype "passive"))
      (node (ref "P4") (pin "8") (pinfunction "G5_8") (pintype "passive"))
      (node (ref "P4") (pin "9") (pinfunction "G4_9") (pintype "passive"))
    )
    (net (code "94") (name "Net-(U5B-USB0_VBUS)") (class "Default")
      (node (ref "R159") (pin "2") (pinfunction "2_2") (pintype "passive"))
      (node (ref "U5") (pin "P15") (pinfunction "USB0_VBUS_P15") (pintype "passive"))
    )
    (net (code "95") (name "SYS_5V") (class "Default")
      (node (ref "C34") (pin "1") (pinfunction "1_1") (pintype "passive"))
      (node (ref "U8") (pin "2") (pinfunction "IN_2") (pintype "power_in"))
      (node (ref "U8") (pin "3") (pinfunction "IN_3") (pintype "power_in"))
    )
    (net (code "96") (name "USB_DC") (class "Default")
      (node (ref "C36") (pin "1") (pinfunction "1_1") (pintype "passive"))
      (node (ref "P4") (pin "1") (pinfunction "VB_1") (pintype "passive"))
      (node (ref "R159") (pin "1") (pinfunction "1_1") (pintype "passive"))
      (node (ref "U10") (pin "6") (pinfunction "VBUS_6") (pintype "power_in"))
    )
    (net (code "97") (name "VDD_3V3A") (class "Default")
      (node (ref "R52") (pin "1") (pinfunction "P1_1") (pintype "passive"))
    )
    (net (code "98") (name "VDD_3V3B") (class "Default")
      (node (ref "C155") (pin "2") (pinfunction "2_2") (pintype "passive"))
      (node (ref "R163") (pin "1") (pinfunction "1_1") (pintype "passive"))
      (node (ref "U15") (pin "7") (pinfunction "~{2OE}_7") (pintype "input"))
      (node (ref "U15") (pin "8") (pinfunction "VCC_8") (pintype "power_in"))
    )
    (net (code "99") (name "VDD_ADC") (class "Default")
      (node (ref "R27") (pin "1") (pinfunction "1_1") (pintype "passive"))
    )
    (net (code "100") (name "VRTC") (class "Default")
      (node (ref "R26") (pin "1") (pinfunction "1_1") (pintype "passive"))
    )
    (net (code "101") (name "unconnected-(J1-NC-Pad2)") (class "Default")
      (node (ref "J1") (pin "2") (pinfunction "NC_2") (pintype "passive+no_connect"))
    )
    (net (code "102") (name "unconnected-(J1-NC-Pad3)") (class "Default")
      (node (ref "J1") (pin "3") (pinfunction "NC_3") (pintype "passive+no_connect"))
    )
    (net (code "103") (name "unconnected-(J1-NC-Pad6)") (class "Default")
      (node (ref "J1") (pin "6") (pinfunction "NC_6") (pintype "passive+no_connect"))
    )
    (net (code "104") (name "unconnected-(U5B-UART0_CTSN{slash}UART4_RXD{slash}DCAN1_TX{slash}I2C1_SDA{slash}SPI1_D0{slash}TIMER7{slash}PR1_EDC_SYNC0_OUT{slash}GPIO1_8-PadE18)") (class "Default")
      (node (ref "U5") (pin "E18") (pinfunction "UART0_CTSN/UART4_RXD/DCAN1_TX/I2C1_SDA/SPI1_D0/TIMER7/PR1_EDC_SYNC0_OUT/GPIO1_8_E18") (pintype "bidirectional+no_connect"))
    )
    (net (code "105") (name "unconnected-(U5B-UART0_RTSN{slash}UART4_TXD{slash}DCAN1_RX{slash}I2C1_SCL{slash}SPI1_D1{slash}SPI1_CS0{slash}PR1_EDC_SYNC1_OUT{slash}GPIO1_9-PadE17)") (class "Default")
      (node (ref "U5") (pin "E17") (pinfunction "UART0_RTSN/UART4_TXD/DCAN1_RX/I2C1_SCL/SPI1_D1/SPI1_CS0/PR1_EDC_SYNC1_OUT/GPIO1_9_E17") (pintype "bidirectional+no_connect"))
    )
    (net (code "106") (name "unconnected-(U5B-USB0_CE-PadM15)") (class "Default")
      (node (ref "U5") (pin "M15") (pinfunction "USB0_CE_M15") (pintype "passive+no_connect"))
    )
    (net (code "107") (name "unconnected-(U5B-USB0_DRVVBUS{slash}GPIO0_18-PadF16)") (class "Default")
      (node (ref "U5") (pin "F16") (pinfunction "USB0_DRVVBUS/GPIO0_18_F16") (pintype "passive+no_connect"))
    )
    (net (code "108") (name "unconnected-(U5B-USB1_CE-PadP18)") (class "Default")
      (node (ref "U5") (pin "P18") (pinfunction "USB1_CE_P18") (pintype "passive+no_connect"))
    )
    (net (code "109") (name "unconnected-(U9-ID-Pad3)") (class "Default")
      (node (ref "U9") (pin "3") (pinfunction "ID_3") (pintype "passive"))
    )
    (net (code "110") (name "unconnected-(U9-NC-Pad5)") (class "Default")
      (node (ref "U9") (pin "5") (pinfunction "NC_5") (pintype "passive+no_connect"))
    )
    (net (code "111") (name "unconnected-(U10-NC-Pad5)") (class "Default")
      (node (ref "U10") (pin "5") (pinfunction "NC_5") (pintype "passive"))
    )
  )
)
